# emonBuck_v0_2.net
KiCad netlist of a schematic drawn in EAGLE
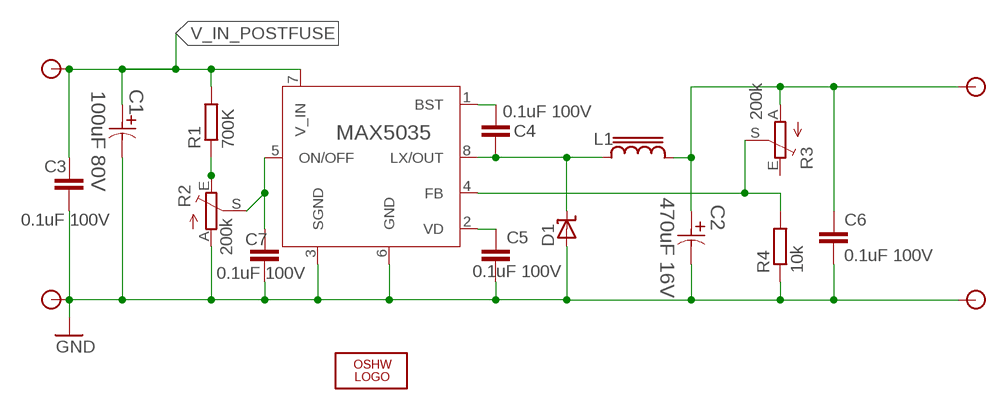
[diagram p0: schematic, sheet 1]

(export (version "E")
  (design (tool "Eeschema 10.0.6"))
  (components
    (comp (ref "C1")
      (value "100uF 80V")
      (footprint "eagle-import:CAPAE1350X1400N")
      (fields (field (name "MPN") "EEVFK1K101Q") (field (name "TOLERANCE") "±20 %"))
      (libsource (lib "eagle-import") (part "EEV--CASE-H13FK1K101Q"))
    )
    (comp (ref "C2")
      (value "470uF 16V")
      (footprint "eagle-import:CAPAE830X1050N")
      (fields (field (name "MPN") "EEE-FK1C471P") (field (name "TOLERANCE") "±20 %"))
      (libsource (lib "eagle-import") (part "EEE--CASE-FFK1C471P"))
    )
    (comp (ref "C3")
      (value "0.1uF 100V")
      (footprint "eagle-import:C0603")
      (libsource (lib "eagle-import") (part "C-EUC0603"))
    )
    (comp (ref "C4")
      (value "0.1uF 100V")
      (footprint "eagle-import:C0603")
      (libsource (lib "eagle-import") (part "C-EUC0603"))
    )
    (comp (ref "C5")
      (value "0.1uF 100V")
      (footprint "eagle-import:C0603")
      (libsource (lib "eagle-import") (part "C-EUC0603"))
    )
    (comp (ref "C6")
      (value "0.1uF 100V")
      (footprint "eagle-import:C0603")
      (libsource (lib "eagle-import") (part "C-EUC0603"))
    )
    (comp (ref "C7")
      (value "0.1uF 100V")
      (footprint "eagle-import:C0603")
      (libsource (lib "eagle-import") (part "C-EUC0603"))
    )
    (comp (ref "D1")
      (value "MBRS1100T3G")
      (footprint "eagle-import:SMB_1")
      (libsource (lib "eagle-import") (part "MBRS1100T3G"))
    )
    (comp (ref "L1")
      (value "SRR1208")
      (footprint "eagle-import:SSR1208")
      (fields (field (name "MPN") "SRR1208-151YL"))
      (libsource (lib "eagle-import") (part "SRR1208"))
    )
    (comp (ref "LOGO1")
      (value "OSHW_LOGO_6MILX0200-NT")
      (footprint "eagle-import:OSHW_6X200_NOTEXT")
      (libsource (lib "eagle-import") (part "OSHW_LOGO_6MILX0200-NT"))
    )
    (comp (ref "MAX5035")
      (value "MAX5035")
      (footprint "eagle-import:21-0111D_SBE-14")
      (fields (field (name "MPN") "MAX5035EASA+"))
      (libsource (lib "eagle-import") (part "MAX5035"))
    )
    (comp (ref "R1")
      (value "700K")
      (footprint "eagle-import:R0603")
      (libsource (lib "eagle-import") (part "R-EU_R0603"))
    )
    (comp (ref "R2")
      (value "200k")
      (footprint "eagle-import:B64W")
      (libsource (lib "eagle-import") (part "TRIM_EU-B64W"))
    )
    (comp (ref "R3")
      (value "200k")
      (footprint "eagle-import:B64W")
      (libsource (lib "eagle-import") (part "TRIM_EU-B64W"))
    )
    (comp (ref "R4")
      (value "10k")
      (footprint "eagle-import:R0603")
      (libsource (lib "eagle-import") (part "R-EU_R0603"))
    )
    (comp (ref "U$1")
      (value "TP0.8MM")
      (footprint "eagle-import:TP0.8")
      (libsource (lib "eagle-import") (part "TP0.8MM"))
    )
    (comp (ref "U$2")
      (value "TP0.8MM")
      (footprint "eagle-import:TP0.8")
      (libsource (lib "eagle-import") (part "TP0.8MM"))
    )
    (comp (ref "U$3")
      (value "TP0.8MM")
      (footprint "eagle-import:TP0.8")
      (libsource (lib "eagle-import") (part "TP0.8MM"))
    )
    (comp (ref "U$4")
      (value "TP0.8MM")
      (footprint "eagle-import:TP0.8")
      (libsource (lib "eagle-import") (part "TP0.8MM"))
    )
  )
  (nets
    (net (code "1") (name "GND") (class "Default")
      (node (ref "C1") (pin "2") (pinfunction "2_2") (pintype "passive"))
      (node (ref "C2") (pin "2") (pinfunction "2_2") (pintype "passive"))
      (node (ref "C3") (pin "2") (pinfunction "2_2") (pintype "passive"))
      (node (ref "C5") (pin "2") (pinfunction "2_2") (pintype "passive"))
      (node (ref "C6") (pin "2") (pinfunction "2_2") (pintype "passive"))
      (node (ref "C7") (pin "2") (pinfunction "2_2") (pintype "passive"))
      (node (ref "D1") (pin "A") (pinfunction "A_A") (pintype "passive"))
      (node (ref "MAX5035") (pin "3") (pinfunction "SGND_3") (pintype "power_in"))
      (node (ref "MAX5035") (pin "6") (pinfunction "GND_6") (pintype "passive"))
      (node (ref "R2") (pin "A") (pinfunction "A_A") (pintype "passive"))
      (node (ref "R4") (pin "1") (pinfunction "1_1") (pintype "passive"))
      (node (ref "U$2") (pin "P$1") (pinfunction "P$1_P$1") (pintype "bidirectional"))
      (node (ref "U$4") (pin "P$1") (pinfunction "P$1_P$1") (pintype "bidirectional"))
    )
    (net (code "2") (name "Net-(C2-Pad1)") (class "Default")
      (node (ref "C2") (pin "1") (pinfunction "1_1") (pintype "passive"))
      (node (ref "C6") (pin "1") (pinfunction "1_1") (pintype "passive"))
      (node (ref "L1") (pin "2") (pinfunction "2_2") (pintype "passive"))
      (node (ref "R3") (pin "A") (pinfunction "A_A") (pintype "passive"))
      (node (ref "U$3") (pin "P$1") (pinfunction "P$1_P$1") (pintype "bidirectional"))
    )
    (net (code "3") (name "Net-(MAX5035-BST)") (class "Default")
      (node (ref "C4") (pin "1") (pinfunction "1_1") (pintype "passive"))
      (node (ref "MAX5035") (pin "1") (pinfunction "BST_1") (pintype "passive"))
    )
    (net (code "4") (name "Net-(MAX5035-FB)") (class "Default")
      (node (ref "MAX5035") (pin "4") (pinfunction "FB_4") (pintype "input"))
      (node (ref "R3") (pin "S") (pinfunction "S_S") (pintype "passive"))
      (node (ref "R4") (pin "2") (pinfunction "2_2") (pintype "passive"))
    )
    (net (code "5") (name "Net-(MAX5035-LX{slash}OUT)") (class "Default")
      (node (ref "C4") (pin "2") (pinfunction "2_2") (pintype "passive"))
      (node (ref "D1") (pin "C") (pinfunction "C_C") (pintype "passive"))
      (node (ref "L1") (pin "1") (pinfunction "1_1") (pintype "passive"))
      (node (ref "MAX5035") (pin "8") (pinfunction "LX/OUT_8") (pintype "output"))
    )
    (net (code "6") (name "Net-(MAX5035-ON{slash}OFF)") (class "Default")
      (node (ref "C7") (pin "1") (pinfunction "1_1") (pintype "passive"))
      (node (ref "MAX5035") (pin "5") (pinfunction "ON/OFF_5") (pintype "input"))
      (node (ref "R2") (pin "S") (pinfunction "S_S") (pintype "passive"))
    )
    (net (code "7") (name "Net-(MAX5035-VD)") (class "Default")
      (node (ref "C5") (pin "1") (pinfunction "1_1") (pintype "passive"))
      (node (ref "MAX5035") (pin "2") (pinfunction "VD_2") (pintype "input"))
    )
    (net (code "8") (name "Net-(R1-Pad1)") (class "Default")
      (node (ref "R1") (pin "1") (pinfunction "1_1") (pintype "passive"))
      (node (ref "R2") (pin "E") (pinfunction "E_E") (pintype "passive"))
    )
    (net (code "9") (name "V_IN_POSTFUSE") (class "Default")
      (node (ref "C1") (pin "1") (pinfunction "1_1") (pintype "passive"))
      (node (ref "C3") (pin "1") (pinfunction "1_1") (pintype "passive"))
      (node (ref "MAX5035") (pin "7") (pinfunction "V_IN_7") (pintype "power_in"))
      (node (ref "R1") (pin "2") (pinfunction "2_2") (pintype "passive"))
      (node (ref "U$1") (pin "P$1") (pinfunction "P$1_P$1") (pintype "bidirectional"))
    )
    (net (code "10") (name "unconnected-(R3-PadE)") (class "Default")
      (node (ref "R3") (pin "E") (pinfunction "E_E") (pintype "passive"))
    )
  )
)
